# battery_shield.net
KiCad netlist of a schematic drawn in EAGLE
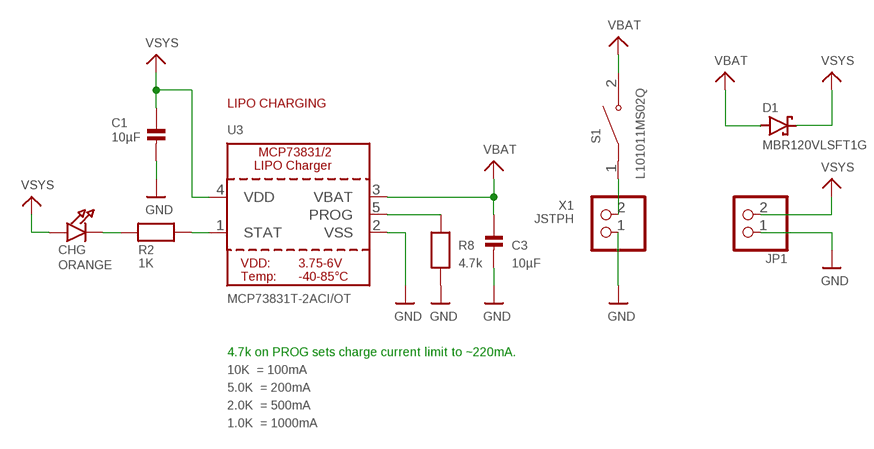
[diagram p0: schematic, sheet 1]

(export (version "E")
  (design (tool "Eeschema 10.0.6"))
  (components
    (comp (ref "C1")
      (value "10µF")
      (footprint "eagle-import:0805-NO")
      (libsource (lib "eagle-import") (part "CAP_CERAMIC0805-NOOUTLINE"))
    )
    (comp (ref "C3")
      (value "10µF")
      (footprint "eagle-import:0805-NO")
      (libsource (lib "eagle-import") (part "CAP_CERAMIC0805-NOOUTLINE"))
    )
    (comp (ref "CHG")
      (value "ORANGE")
      (footprint "eagle-import:CHIPLED_0805_NOOUTLINE")
      (libsource (lib "eagle-import") (part "LED0805_NOOUTLINE"))
    )
    (comp (ref "D1")
      (value "MBR120VLSFT1G")
      (footprint "eagle-import:SOD123FL")
      (libsource (lib "eagle-import") (part "SMF5.0AT1"))
    )
    (comp (ref "JP1")
      (value "PINHD-1X2")
      (footprint "eagle-import:1X02")
      (libsource (lib "eagle-import") (part "PINHD-1X2"))
    )
    (comp (ref "R2")
      (value "1K")
      (footprint "eagle-import:0603-NO")
      (libsource (lib "eagle-import") (part "RESISTOR_0603_NOOUT"))
    )
    (comp (ref "R8")
      (value "4.7k")
      (footprint "eagle-import:0603-NO")
      (libsource (lib "eagle-import") (part "RESISTOR_0603_NOOUT"))
    )
    (comp (ref "S1")
      (value "L101011MS02Q")
      (footprint "eagle-import:SW_L101011MS02Q")
      (fields (field (name "MF") "C&K"))
      (libsource (lib "eagle-import") (part "L101011MS02Q"))
    )
    (comp (ref "U3")
      (value "MCP73831T-2ACI/OT")
      (footprint "eagle-import:SOT23-5")
      (libsource (lib "eagle-import") (part "MCP73831/2"))
    )
    (comp (ref "X1")
      (value "JSTPH")
      (footprint "eagle-import:JSTPH2")
      (libsource (lib "eagle-import") (part "CON_JST_PH_2PIN"))
    )
  )
  (nets
    (net (code "1") (name "GND") (class "Default")
      (node (ref "C1") (pin "2") (pinfunction "2_2") (pintype "passive"))
      (node (ref "C3") (pin "2") (pinfunction "2_2") (pintype "passive"))
      (node (ref "JP1") (pin "1") (pinfunction "1_1") (pintype "passive"))
      (node (ref "R8") (pin "2") (pinfunction "2_2") (pintype "passive"))
      (node (ref "U3") (pin "2") (pinfunction "VSS_2") (pintype "power_in"))
      (node (ref "X1") (pin "1") (pinfunction "1_1") (pintype "passive"))
    )
    (net (code "2") (name "Net-(CHG-PadC)") (class "Default")
      (node (ref "CHG") (pin "C") (pinfunction "C_C") (pintype "passive"))
      (node (ref "R2") (pin "1") (pinfunction "1_1") (pintype "passive"))
    )
    (net (code "3") (name "Net-(S1-Pad1)") (class "Default")
      (node (ref "S1") (pin "1") (pinfunction "1_1") (pintype "passive"))
      (node (ref "X1") (pin "2") (pinfunction "2_2") (pintype "passive"))
    )
    (net (code "4") (name "Net-(U3-PROG)") (class "Default")
      (node (ref "R8") (pin "1") (pinfunction "1_1") (pintype "passive"))
      (node (ref "U3") (pin "5") (pinfunction "PROG_5") (pintype "input"))
    )
    (net (code "5") (name "Net-(U3-STAT)") (class "Default")
      (node (ref "R2") (pin "2") (pinfunction "2_2") (pintype "passive"))
      (node (ref "U3") (pin "1") (pinfunction "STAT_1") (pintype "output"))
    )
    (net (code "6") (name "VBAT") (class "Default")
      (node (ref "C3") (pin "1") (pinfunction "1_1") (pintype "passive"))
      (node (ref "D1") (pin "A") (pinfunction "A_A") (pintype "passive"))
      (node (ref "S1") (pin "2") (pinfunction "2_2") (pintype "passive"))
      (node (ref "U3") (pin "3") (pinfunction "VBAT_3") (pintype "power_in"))
    )
    (net (code "7") (name "VSYS") (class "Default")
      (node (ref "C1") (pin "1") (pinfunction "1_1") (pintype "passive"))
      (node (ref "CHG") (pin "A") (pinfunction "A_A") (pintype "passive"))
      (node (ref "D1") (pin "C") (pinfunction "C_C") (pintype "passive"))
      (node (ref "JP1") (pin "2") (pinfunction "2_2") (pintype "passive"))
      (node (ref "U3") (pin "4") (pinfunction "VDD_4") (pintype "power_in"))
    )
  )
)
